# CAMERA.net
KiCad netlist of a schematic drawn in Altium Designer
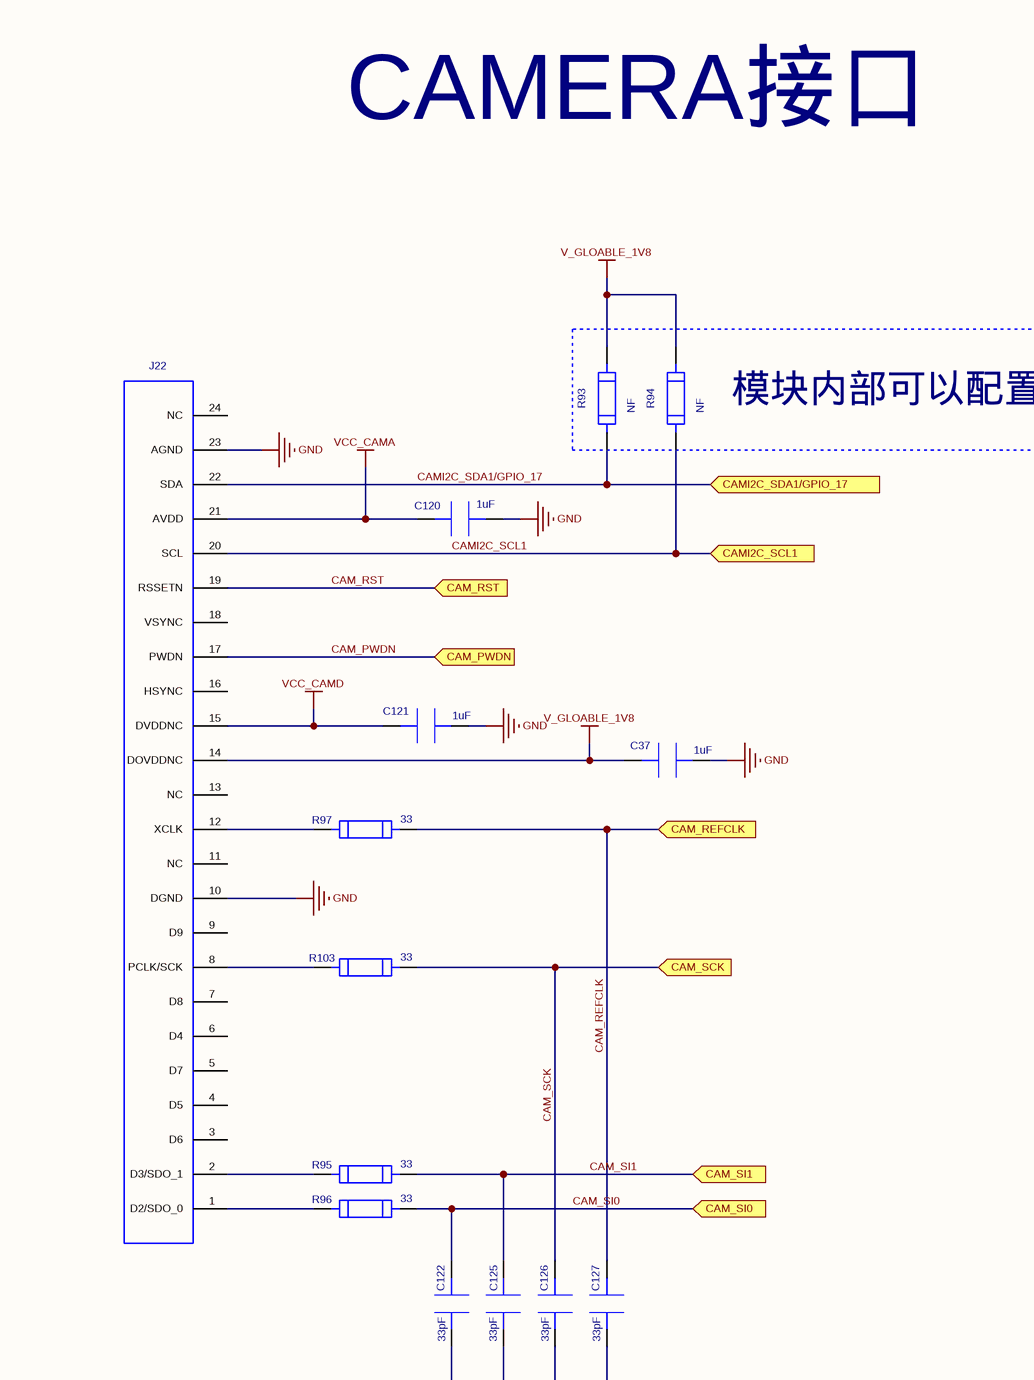
[diagram p0: CAMERA.SchDoc, top left]
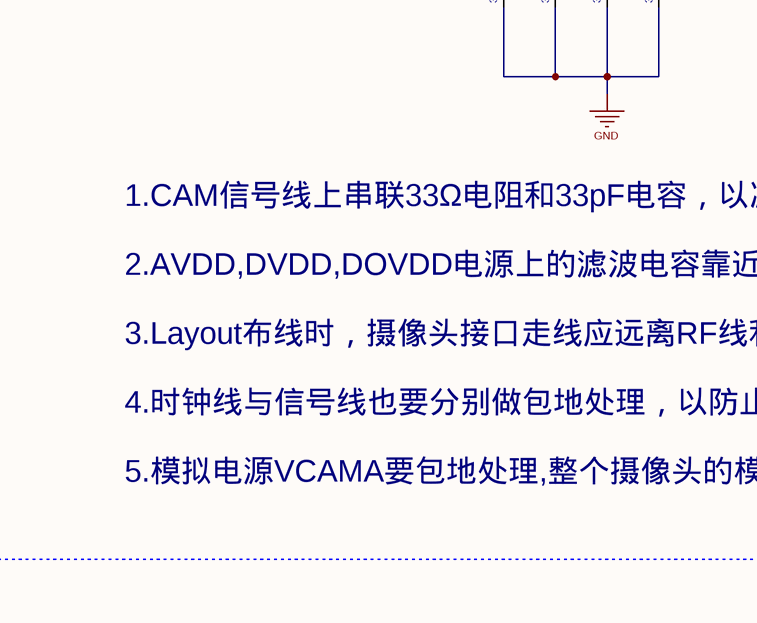
[diagram p1: CAMERA.SchDoc, bottom left]
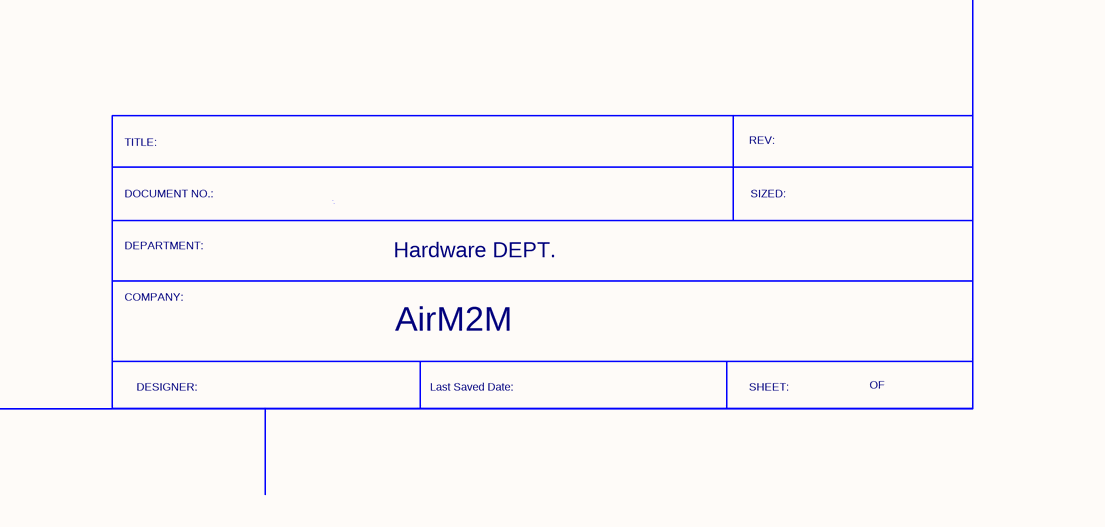
[diagram p2: CAMERA.SchDoc, bottom right]

(export (version "E")
  (design (tool "Eeschema 10.0.6"))
  (components
    (comp (ref "C37")
      (value "1uF")
      (footprint "SC0402")
      (description "CAP CER X5R;1uF;+/-10%;6.3V;0402;0.5mm;ROHS")
      (fields (field (name "TOLERANCE") "+/-10%") (field (name "Comment") "CAP-1UF-0402-X5R"))
      (libsource (lib "*") (part "CAP-1UF-0402-X5R"))
    )
    (comp (ref "C120")
      (value "1uF")
      (footprint "SC0402")
      (description "CAP CER X5R;1uF;+/-10%;6.3V;0402;0.5mm;ROHS")
      (fields (field (name "TOLERANCE") "+/-10%") (field (name "Comment") "CAP-1UF-0402-X5R"))
      (libsource (lib "*") (part "CAP-1UF-0402-X5R"))
    )
    (comp (ref "C121")
      (value "1uF")
      (footprint "SC0402")
      (description "CAP CER X5R;1uF;+/-10%;6.3V;0402;0.5mm;ROHS")
      (fields (field (name "TOLERANCE") "+/-10%") (field (name "Comment") "CAP-1UF-0402-X5R"))
      (libsource (lib "*") (part "CAP-1UF-0402-X5R"))
    )
    (comp (ref "C122")
      (value "33pF")
      (footprint "SC0402")
      (description "CAP CER C0G;33PF;+/-5%;50V;0402;0.5mm;ROHS")
      (fields (field (name "TOLERANCE") "+/-5%") (field (name "Comment") "CAP-33PF-0402-C0G"))
      (libsource (lib "*") (part "CAP-33PF-0402-C0G"))
    )
    (comp (ref "C125")
      (value "33pF")
      (footprint "SC0402")
      (description "CAP CER C0G;33PF;+/-5%;50V;0402;0.5mm;ROHS")
      (fields (field (name "TOLERANCE") "+/-5%") (field (name "Comment") "CAP-33PF-0402-C0G"))
      (libsource (lib "*") (part "CAP-33PF-0402-C0G"))
    )
    (comp (ref "C126")
      (value "33pF")
      (footprint "SC0402")
      (description "CAP CER C0G;33PF;+/-5%;50V;0402;0.5mm;ROHS")
      (fields (field (name "TOLERANCE") "+/-5%") (field (name "Comment") "CAP-33PF-0402-C0G"))
      (libsource (lib "*") (part "CAP-33PF-0402-C0G"))
    )
    (comp (ref "C127")
      (value "33pF")
      (footprint "SC0402")
      (description "CAP CER C0G;33PF;+/-5%;50V;0402;0.5mm;ROHS")
      (fields (field (name "TOLERANCE") "+/-5%") (field (name "Comment") "CAP-33PF-0402-C0G"))
      (libsource (lib "*") (part "CAP-33PF-0402-C0G"))
    )
    (comp (ref "J22")
      (value "FPC-24PIN-0.5MM-Y")
      (footprint "FPC-24PIN-0.5MM")
      (libsource (lib "*") (part "FPC-24PIN-0.5MM-Y"))
    )
    (comp (ref "R93")
      (value "NF")
      (footprint "SR0402-NF")
      (fields (field (name "TOLERANCE") "+/-5%") (field (name "Comment") "RES-0402-NF"))
      (libsource (lib "*") (part "RES-0402-NF"))
    )
    (comp (ref "R94")
      (value "NF")
      (footprint "SR0402-NF")
      (fields (field (name "TOLERANCE") "+/-5%") (field (name "Comment") "RES-0402-NF"))
      (libsource (lib "*") (part "RES-0402-NF"))
    )
    (comp (ref "R95")
      (value "33")
      (footprint "SR0402")
      (description "RES FILM;22;+/-5%;1/16W;0402;0.4mm;ROHS")
      (fields (field (name "TOLERANCE") "+/-5%") (field (name "Comment") "RES-22-0402"))
      (libsource (lib "*") (part "RES-22-0402"))
    )
    (comp (ref "R96")
      (value "33")
      (footprint "SR0402")
      (description "RES FILM;22;+/-5%;1/16W;0402;0.4mm;ROHS")
      (fields (field (name "TOLERANCE") "+/-5%") (field (name "Comment") "RES-22-0402"))
      (libsource (lib "*") (part "RES-22-0402"))
    )
    (comp (ref "R97")
      (value "33")
      (footprint "SR0402")
      (description "RES FILM;22;+/-5%;1/16W;0402;0.4mm;ROHS")
      (fields (field (name "TOLERANCE") "+/-5%") (field (name "Comment") "RES-22-0402"))
      (libsource (lib "*") (part "RES-22-0402"))
    )
    (comp (ref "R103")
      (value "33")
      (footprint "SR0402")
      (description "RES FILM;22;+/-5%;1/16W;0402;0.4mm;ROHS")
      (fields (field (name "TOLERANCE") "+/-5%") (field (name "Comment") "RES-22-0402"))
      (libsource (lib "*") (part "RES-22-0402"))
    )
  )
  (nets
    (net (code "1") (name "/CAMI2C_SCL1") (class "Default")
      (node (ref "J22") (pin "20") (pinfunction "SCL_20") (pintype "passive"))
      (node (ref "R94") (pin "1") (pinfunction "1_1") (pintype "passive"))
    )
    (net (code "2") (name "/CAMI2C_SDA1{slash}GPIO_17") (class "Default")
      (node (ref "J22") (pin "22") (pinfunction "SDA_22") (pintype "passive"))
      (node (ref "R93") (pin "1") (pinfunction "1_1") (pintype "passive"))
    )
    (net (code "3") (name "/CAM_PWDN") (class "Default")
      (node (ref "J22") (pin "17") (pinfunction "PWDN_17") (pintype "passive"))
    )
    (net (code "4") (name "/CAM_REFCLK") (class "Default")
      (node (ref "C127") (pin "2") (pinfunction "2_2") (pintype "passive"))
      (node (ref "R97") (pin "2") (pinfunction "2_2") (pintype "passive"))
    )
    (net (code "5") (name "/CAM_RST") (class "Default")
      (node (ref "J22") (pin "19") (pinfunction "RSSETN_19") (pintype "passive"))
    )
    (net (code "6") (name "/CAM_SCK") (class "Default")
      (node (ref "C126") (pin "2") (pinfunction "2_2") (pintype "passive"))
      (node (ref "R103") (pin "2") (pinfunction "2_2") (pintype "passive"))
    )
    (net (code "7") (name "/CAM_SI0") (class "Default")
      (node (ref "C122") (pin "2") (pinfunction "2_2") (pintype "passive"))
      (node (ref "R96") (pin "2") (pinfunction "2_2") (pintype "passive"))
    )
    (net (code "8") (name "/CAM_SI1") (class "Default")
      (node (ref "C125") (pin "2") (pinfunction "2_2") (pintype "passive"))
      (node (ref "R95") (pin "2") (pinfunction "2_2") (pintype "passive"))
    )
    (net (code "9") (name "GND") (class "Default")
      (node (ref "C120") (pin "1") (pinfunction "1_1") (pintype "passive"))
      (node (ref "C121") (pin "2") (pinfunction "2_2") (pintype "passive"))
      (node (ref "C122") (pin "1") (pinfunction "1_1") (pintype "passive"))
      (node (ref "C125") (pin "1") (pinfunction "1_1") (pintype "passive"))
      (node (ref "C126") (pin "1") (pinfunction "1_1") (pintype "passive"))
      (node (ref "C127") (pin "1") (pinfunction "1_1") (pintype "passive"))
      (node (ref "C37") (pin "2") (pinfunction "2_2") (pintype "passive"))
      (node (ref "J22") (pin "10") (pinfunction "DGND_10") (pintype "passive"))
      (node (ref "J22") (pin "23") (pinfunction "AGND_23") (pintype "passive"))
      (node (ref "J22") (pin "25") (pinfunction "GND_25") (pintype "power_in"))
      (node (ref "J22") (pin "26") (pinfunction "GND_26") (pintype "power_in"))
    )
    (net (code "10") (name "Net-(J22-D2{slash}SDO_0)") (class "Default")
      (node (ref "J22") (pin "1") (pinfunction "D2/SDO_0_1") (pintype "passive"))
      (node (ref "R96") (pin "1") (pinfunction "1_1") (pintype "passive"))
    )
    (net (code "11") (name "Net-(J22-D3{slash}SDO_1)") (class "Default")
      (node (ref "J22") (pin "2") (pinfunction "D3/SDO_1_2") (pintype "passive"))
      (node (ref "R95") (pin "1") (pinfunction "1_1") (pintype "passive"))
    )
    (net (code "12") (name "Net-(J22-PCLK{slash}SCK)") (class "Default")
      (node (ref "J22") (pin "8") (pinfunction "PCLK/SCK_8") (pintype "passive"))
      (node (ref "R103") (pin "1") (pinfunction "1_1") (pintype "passive"))
    )
    (net (code "13") (name "Net-(J22-XCLK)") (class "Default")
      (node (ref "J22") (pin "12") (pinfunction "XCLK_12") (pintype "passive"))
      (node (ref "R97") (pin "1") (pinfunction "1_1") (pintype "passive"))
    )
    (net (code "14") (name "VCC_CAMA") (class "Default")
      (node (ref "C120") (pin "2") (pinfunction "2_2") (pintype "passive"))
      (node (ref "J22") (pin "21") (pinfunction "AVDD_21") (pintype "passive"))
    )
    (net (code "15") (name "VCC_CAMD") (class "Default")
      (node (ref "C121") (pin "1") (pinfunction "1_1") (pintype "passive"))
      (node (ref "J22") (pin "15") (pinfunction "DVDDNC_15") (pintype "passive"))
    )
    (net (code "16") (name "V_GLOABLE_1V8") (class "Default")
      (node (ref "C37") (pin "1") (pinfunction "1_1") (pintype "passive"))
      (node (ref "J22") (pin "14") (pinfunction "DOVDDNC_14") (pintype "passive"))
      (node (ref "R93") (pin "2") (pinfunction "2_2") (pintype "passive"))
      (node (ref "R94") (pin "2") (pinfunction "2_2") (pintype "passive"))
    )
    (net (code "17") (name "unconnected-(J22-D4-Pad6)") (class "Default")
      (node (ref "J22") (pin "6") (pinfunction "D4_6") (pintype "passive"))
    )
    (net (code "18") (name "unconnected-(J22-D5-Pad4)") (class "Default")
      (node (ref "J22") (pin "4") (pinfunction "D5_4") (pintype "passive"))
    )
    (net (code "19") (name "unconnected-(J22-D6-Pad3)") (class "Default")
      (node (ref "J22") (pin "3") (pinfunction "D6_3") (pintype "passive"))
    )
    (net (code "20") (name "unconnected-(J22-D7-Pad5)") (class "Default")
      (node (ref "J22") (pin "5") (pinfunction "D7_5") (pintype "passive"))
    )
    (net (code "21") (name "unconnected-(J22-D8-Pad7)") (class "Default")
      (node (ref "J22") (pin "7") (pinfunction "D8_7") (pintype "passive"))
    )
    (net (code "22") (name "unconnected-(J22-D9-Pad9)") (class "Default")
      (node (ref "J22") (pin "9") (pinfunction "D9_9") (pintype "passive"))
    )
    (net (code "23") (name "unconnected-(J22-HSYNC-Pad16)") (class "Default")
      (node (ref "J22") (pin "16") (pinfunction "HSYNC_16") (pintype "passive"))
    )
    (net (code "24") (name "unconnected-(J22-NC-Pad11)") (class "Default")
      (node (ref "J22") (pin "11") (pinfunction "NC_11") (pintype "passive"))
    )
    (net (code "25") (name "unconnected-(J22-NC-Pad13)") (class "Default")
      (node (ref "J22") (pin "13") (pinfunction "NC_13") (pintype "passive"))
    )
    (net (code "26") (name "unconnected-(J22-NC-Pad24)") (class "Default")
      (node (ref "J22") (pin "24") (pinfunction "NC_24") (pintype "passive"))
    )
    (net (code "27") (name "unconnected-(J22-VSYNC-Pad18)") (class "Default")
      (node (ref "J22") (pin "18") (pinfunction "VSYNC_18") (pintype "passive"))
    )
  )
)
